# RV-3028_Real-Time_Clock.net
KiCad netlist of a schematic drawn in Altium Designer
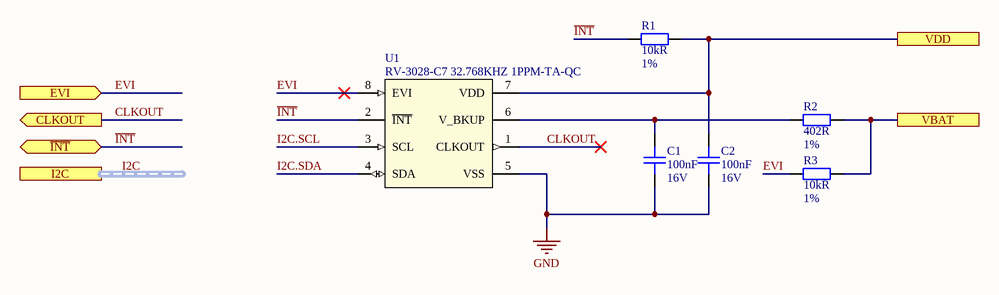
[diagram p0: RV-3028_Real-Time_Clock.SchDoc]

(export (version "E")
  (design (tool "Eeschema 10.0.6"))
  (components
    (comp (ref "C1")
      (value "CAP CER 0.1UF 16V X7R 0402")
      (footprint "C0402")
      (description "0.1µF ±10% 16V Ceramic Capacitor X7R 0402 (1005 Metric)")
      (fields
        (field (name "MANUFACTURER PART NUMBER") "CC0402KRX7R7BB104")
        (field (name "MANUFACTURER") "Yageo")
        (field (name "CAPACITANCE") "100nF")
        (field (name "VOLTAGE") "16V")
      )
      (libsource (lib "capacitors_smd") (part "CAP CER 0.1UF 16V X7R 0402"))
    )
    (comp (ref "C2")
      (value "CAP CER 0.1UF 16V X7R 0402")
      (footprint "C0402")
      (description "0.1µF ±10% 16V Ceramic Capacitor X7R 0402 (1005 Metric)")
      (fields
        (field (name "MANUFACTURER PART NUMBER") "CC0402KRX7R7BB104")
        (field (name "MANUFACTURER") "Yageo")
        (field (name "CAPACITANCE") "100nF")
        (field (name "VOLTAGE") "16V")
      )
      (libsource (lib "capacitors_smd") (part "CAP CER 0.1UF 16V X7R 0402"))
    )
    (comp (ref "R1")
      (value "RES SMD 10K OHM 1% 1/16W 0402")
      (footprint "R0402")
      (description "10 kOhms ±1% 0.063W, 1/16W Chip Resistor 0402 (1005 Metric) Moisture Resistant Thick Film")
      (fields
        (field (name "MANUFACTURER PART NUMBER") "RC0402FR-0710KP")
        (field (name "MANUFACTURER") "Yageo")
        (field (name "RESISTANCE") "10kR")
        (field (name "TOLERANCE") "1%")
      )
      (libsource (lib "resistors_smd") (part "RES SMD 10K OHM 1% 1/16W 0402"))
    )
    (comp (ref "R2")
      (value "RES SMD 402 OHM 1% 1/16W 0402")
      (footprint "R0402")
      (description "402 Ohms ±1% 0.063W, 1/16W Chip Resistor 0402 (1005 Metric) Moisture Resistant Thick Film")
      (fields
        (field (name "MANUFACTURER") "Yageo")
        (field (name "MANUFACTURER PART NUMBER") "RC0402FR-07402RL")
        (field (name "RESISTANCE") "402R")
        (field (name "TOLERANCE") "1%")
      )
      (libsource (lib "resistors_smd") (part "RES SMD 402 OHM 1% 1/16W 0402"))
    )
    (comp (ref "R3")
      (value "RES SMD 10K OHM 1% 1/16W 0402")
      (footprint "R0402")
      (description "10 kOhms ±1% 0.063W, 1/16W Chip Resistor 0402 (1005 Metric) Moisture Resistant Thick Film")
      (fields
        (field (name "MANUFACTURER PART NUMBER") "RC0402FR-0710KP")
        (field (name "MANUFACTURER") "Yageo")
        (field (name "RESISTANCE") "10kR")
        (field (name "TOLERANCE") "1%")
      )
      (libsource (lib "resistors_smd") (part "RES SMD 10K OHM 1% 1/16W 0402"))
    )
    (comp (ref "U1")
      (value "RV-3028-C7 32.768KHZ 1PPM-TA-QC")
      (footprint "8-SON (3.2x1.5)")
      (description "2-Bit Bidirectional Voltage-Level Translator for Open-Drain Application")
      (fields (field (name "MANUFACTURER") "Micro Crystal"))
      (libsource (lib "BLDC_Motor_Driver") (part "IC RV-3028 RTC CLK/CALENDAR I2C 8-SMT"))
    )
  )
  (nets
    (net (code "2") (name "/CLKOUT") (class "Default")
      (node (ref "U1") (pin "1") (pinfunction "CLKOUT_1") (pintype "output+no_connect"))
    )
    (net (code "3") (name "/EVI") (class "Default")
      (node (ref "R3") (pin "2") (pinfunction "2_2") (pintype "passive"))
      (node (ref "U1") (pin "8") (pinfunction "EVI_8") (pintype "input"))
    )
    (net (code "4") (name "/I2C.SCL") (class "Default")
      (node (ref "U1") (pin "3") (pinfunction "SCL_3") (pintype "input"))
    )
    (net (code "5") (name "/I2C.SDA") (class "Default")
      (node (ref "U1") (pin "4") (pinfunction "SDA_4") (pintype "bidirectional"))
    )
    (net (code "6") (name "/INT") (class "Default")
      (node (ref "R1") (pin "2") (pinfunction "2_2") (pintype "passive"))
      (node (ref "U1") (pin "2") (pinfunction "INT_2") (pintype "passive"))
    )
    (net (code "7") (name "/VBAT") (class "Default")
      (node (ref "R2") (pin "2") (pinfunction "2_2") (pintype "passive"))
      (node (ref "R3") (pin "1") (pinfunction "1_1") (pintype "passive"))
    )
    (net (code "8") (name "/VDD") (class "Default")
      (node (ref "C2") (pin "2") (pinfunction "2_2") (pintype "passive"))
      (node (ref "R1") (pin "1") (pinfunction "1_1") (pintype "passive"))
      (node (ref "U1") (pin "7") (pinfunction "VDD_7") (pintype "power_in"))
    )
    (net (code "10") (name "GND") (class "Default")
      (node (ref "C1") (pin "1") (pinfunction "1_1") (pintype "passive"))
      (node (ref "C2") (pin "1") (pinfunction "1_1") (pintype "passive"))
      (node (ref "U1") (pin "5") (pinfunction "VSS_5") (pintype "power_in"))
    )
    (net (code "11") (name "Net-(U1-V_BKUP)") (class "Default")
      (node (ref "C1") (pin "2") (pinfunction "2_2") (pintype "passive"))
      (node (ref "R2") (pin "1") (pinfunction "1_1") (pintype "passive"))
      (node (ref "U1") (pin "6") (pinfunction "V_BKUP_6") (pintype "power_in"))
    )
  )
)
